# ethernet.net
KiCad netlist of a schematic drawn in Altium Designer
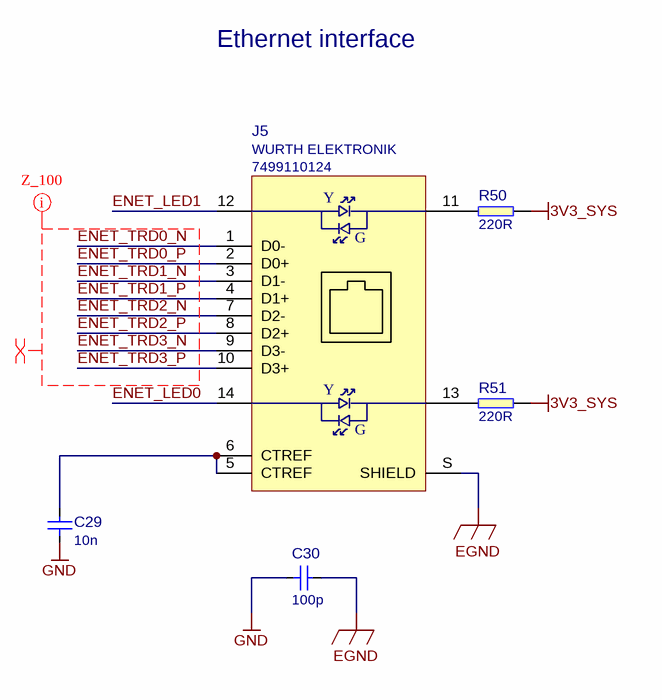
[diagram p0: ethernet.SchDoc]

(export (version "E")
  (design (tool "Eeschema 10.0.6"))
  (components
    (comp (ref "C29")
      (value "10n")
      (footprint "0603")
      (description "MLCC SMT Capacitor 10 nF 0603")
      (fields (field (name "PARTNUMBER") "C_10n_0603") (field (name "MANUFACTURER") "AVX"))
      (libsource (lib "jetson-nano-baseboard") (part "C_10n_0603"))
    )
    (comp (ref "C30")
      (value "100p")
      (footprint "0603")
      (description "MLCC SMT Capacitor 100pF 0603")
      (fields (field (name "PARTNUMBER") "C_100p_0603") (field (name "MANUFACTURER") "Walsin"))
      (libsource (lib "jetson-nano-baseboard") (part "C_100p_0603"))
    )
    (comp (ref "J5")
      (value "WE_7499110124")
      (footprint "WE_7499110124")
      (description "LAN-Transformer WE-RJ45LAN 10/100/1000 BaseT")
      (fields (field (name "MANUFACTURER") "WURTH ELEKTRONIK") (field (name "PARTSYMBOL") "7499110124"))
      (libsource (lib "jetson-nano-baseboard") (part "WE_7499111447"))
    )
    (comp (ref "R50")
      (value "220R")
      (footprint "0402")
      (description "RES, 220R, 0402")
      (fields (field (name "PARTNUMBER") "R_220R_0402") (field (name "MANUFACTURER") "TE Connectivity"))
      (libsource (lib "") (part "R_220R_0402_1"))
    )
    (comp (ref "R51")
      (value "220R")
      (footprint "0402")
      (description "RES, 220R, 0402")
      (fields (field (name "PARTNUMBER") "R_220R_0402") (field (name "MANUFACTURER") "TE Connectivity"))
      (libsource (lib "jetson-nano-baseboard") (part "R_220R_0402"))
    )
  )
  (nets
    (net (code "1") (name "/ENET_LED0") (class "Default")
      (node (ref "J5") (pin "14") (pinfunction "14_14") (pintype "passive"))
    )
    (net (code "2") (name "/ENET_LED1") (class "Default")
      (node (ref "J5") (pin "12") (pinfunction "12_12") (pintype "passive"))
    )
    (net (code "3") (name "/ENET_TRD0_N") (class "Default")
      (node (ref "J5") (pin "1") (pinfunction "D0-_1") (pintype "passive"))
    )
    (net (code "4") (name "/ENET_TRD0_P") (class "Default")
      (node (ref "J5") (pin "2") (pinfunction "D0+_2") (pintype "passive"))
    )
    (net (code "5") (name "/ENET_TRD1_N") (class "Default")
      (node (ref "J5") (pin "3") (pinfunction "D1-_3") (pintype "passive"))
    )
    (net (code "6") (name "/ENET_TRD1_P") (class "Default")
      (node (ref "J5") (pin "4") (pinfunction "D1+_4") (pintype "passive"))
    )
    (net (code "7") (name "/ENET_TRD2_N") (class "Default")
      (node (ref "J5") (pin "7") (pinfunction "D2-_7") (pintype "passive"))
    )
    (net (code "8") (name "/ENET_TRD2_P") (class "Default")
      (node (ref "J5") (pin "8") (pinfunction "D2+_8") (pintype "passive"))
    )
    (net (code "9") (name "/ENET_TRD3_N") (class "Default")
      (node (ref "J5") (pin "9") (pinfunction "D3-_9") (pintype "passive"))
    )
    (net (code "10") (name "/ENET_TRD3_P") (class "Default")
      (node (ref "J5") (pin "10") (pinfunction "D3+_10") (pintype "passive"))
    )
    (net (code "11") (name "3V3_SYS") (class "Default")
      (node (ref "R50") (pin "2") (pintype "passive"))
      (node (ref "R51") (pin "1") (pintype "passive"))
    )
    (net (code "12") (name "EGND") (class "Default")
      (node (ref "C30") (pin "2") (pinfunction "2_2") (pintype "passive"))
      (node (ref "J5") (pin "S") (pinfunction "SHIELD_S") (pintype "passive"))
    )
    (net (code "13") (name "GND") (class "Default")
      (node (ref "C29") (pin "1") (pinfunction "1_1") (pintype "passive"))
      (node (ref "C30") (pin "1") (pinfunction "1_1") (pintype "passive"))
    )
    (net (code "14") (name "Net-(C29-Pad2)") (class "Default")
      (node (ref "C29") (pin "2") (pinfunction "2_2") (pintype "passive"))
      (node (ref "J5") (pin "5") (pinfunction "CTREF_5") (pintype "passive"))
      (node (ref "J5") (pin "6") (pinfunction "CTREF_6") (pintype "passive"))
    )
    (net (code "15") (name "Net-(J5-Pad11)") (class "Default")
      (node (ref "J5") (pin "11") (pinfunction "11_11") (pintype "passive"))
      (node (ref "R50") (pin "1") (pintype "passive"))
    )
    (net (code "16") (name "Net-(J5-Pad13)") (class "Default")
      (node (ref "J5") (pin "13") (pinfunction "13_13") (pintype "passive"))
      (node (ref "R51") (pin "2") (pintype "passive"))
    )
  )
)
